# Schematic_Bottom_Rev2.net
KiCad netlist of a schematic drawn in Altium Designer
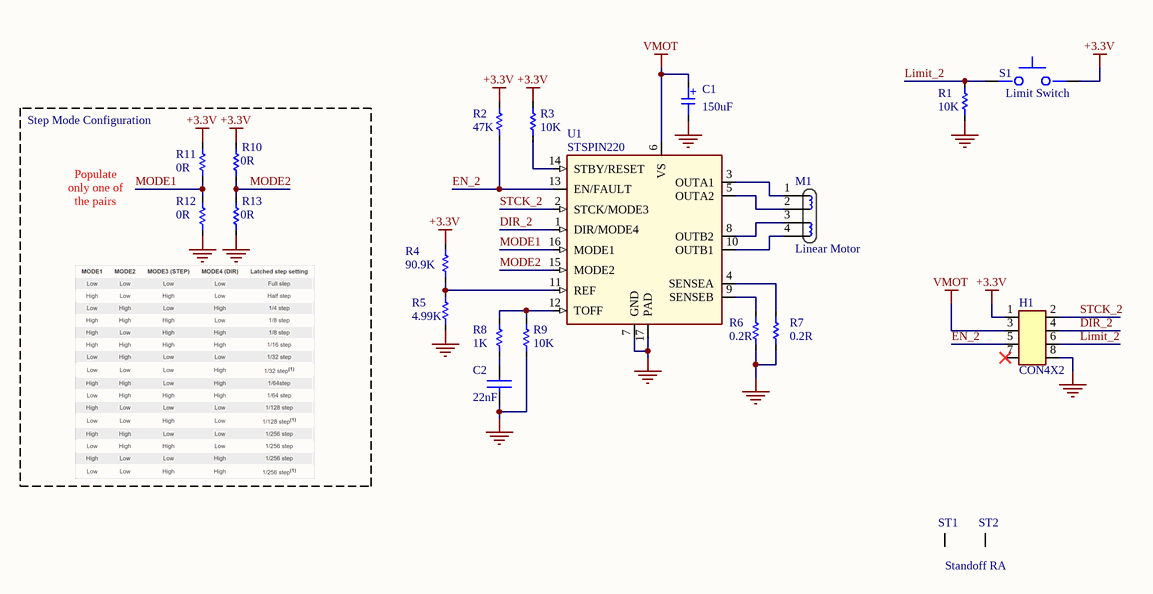
[diagram p0: Schematic_Bottom_Rev2.SchDoc]

(export (version "E")
  (design (tool "Eeschema 10.0.6"))
  (components
    (comp (ref "C1")
      (value "150uF")
      (footprint "CAP_SM_CAN_0.250_DIA")
      (description "CAP 150uF, 10V SMT")
      (fields (field (name "PART_NUMBER") "C242018") (field (name "MANUFACTURER") "Suncon"))
      (libsource (lib "MAR") (part "CAP_ELEC_SMT"))
    )
    (comp (ref "C2")
      (value "22nF")
      (footprint "CAPC1005X56N")
      (description "CAP 22nF 16V 0402")
      (fields (field (name "PART_NUMBER") "C318579") (field (name "MANUFACTURER") "Samsung"))
      (libsource (lib "MAR") (part "CAP_0402"))
    )
    (comp (ref "H1")
      (value "CON4X2")
      (footprint "RCPT2X4")
      (description "CONN REPT 4X2 POS .100\" RA")
      (fields (field (name "PART_NUMBER") "C92271") (field (name "MANUFACTURER") "CONNFLY"))
      (libsource (lib "MAR") (part "CON4X2_F"))
    )
    (comp (ref "M1")
      (value "Linear Motor")
      (footprint "Motor_Mini_Linear_1")
      (description "MTR,LINEAR,SMT")
      (fields (field (name "PART_NUMBER") "shorturl.at/cQ269"))
      (libsource (lib "MAR") (part "Motor_Mini_Linear"))
    )
    (comp (ref "R1")
      (value "10K")
      (footprint "RESC1005X40L")
      (description "RES 10K 0402")
      (fields (field (name "PART_NUMBER") "C25744") (field (name "MANUFACTURER") "Uniroyal"))
      (libsource (lib "MAR") (part "RES_0402"))
    )
    (comp (ref "R2")
      (value "47K")
      (footprint "RESC1005X40L")
      (description "RES 47K 0402")
      (fields (field (name "PART_NUMBER") "C25792") (field (name "MANUFACTURER") "Uniroyal"))
      (libsource (lib "MAR") (part "RES_0402"))
    )
    (comp (ref "R3")
      (value "10K")
      (footprint "RESC1005X40L")
      (description "RES 10K 0402")
      (fields (field (name "PART_NUMBER") "C25744") (field (name "MANUFACTURER") "Uniroyal"))
      (libsource (lib "MAR") (part "RES_0402"))
    )
    (comp (ref "R4")
      (value "90.9K")
      (footprint "RESC1005X40L")
      (description "RES 90.9K 0402")
      (fields (field (name "PART_NUMBER") "C26989") (field (name "MANUFACTURER") "Uniroyal"))
      (libsource (lib "MAR") (part "RES_0402"))
    )
    (comp (ref "R5")
      (value "4.99K")
      (footprint "RESC1005X40L")
      (description "RES 4.99K 0402")
      (fields (field (name "PART_NUMBER") "C25903") (field (name "MANUFACTURER") "Uniroyal"))
      (libsource (lib "MAR") (part "RES_0402"))
    )
    (comp (ref "R6")
      (value "0.2R")
      (footprint "RESC1005X40L")
      (description "RES 0.2R 0402")
      (fields (field (name "PART_NUMBER") "C270629") (field (name "MANUFACTURER") "Uniroyal"))
      (libsource (lib "MAR") (part "RES_0402"))
    )
    (comp (ref "R7")
      (value "0.2R")
      (footprint "RESC1005X40L")
      (description "RES 0.2R 0402")
      (fields (field (name "PART_NUMBER") "C270629") (field (name "MANUFACTURER") "Uniroyal"))
      (libsource (lib "MAR") (part "RES_0402"))
    )
    (comp (ref "R8")
      (value "1K")
      (footprint "RESC1005X40L")
      (description "RES 1K 0402")
      (fields (field (name "PART_NUMBER") "C11702") (field (name "MANUFACTURER") "Uniroyal"))
      (libsource (lib "MAR") (part "RES_0402"))
    )
    (comp (ref "R9")
      (value "10K")
      (footprint "RESC1005X40L")
      (description "RES 10K 0402")
      (fields (field (name "PART_NUMBER") "C25744") (field (name "MANUFACTURER") "Uniroyal"))
      (libsource (lib "MAR") (part "RES_0402"))
    )
    (comp (ref "R10")
      (value "0R")
      (footprint "RESC1005X40L")
      (description "RES 0R 0402")
      (fields (field (name "MANUFACTURER") "Uniroyal"))
      (libsource (lib "MAR") (part "RES_0402"))
    )
    (comp (ref "R11")
      (value "0R")
      (footprint "RESC1005X40L")
      (description "RES 0R 0402")
      (fields (field (name "MANUFACTURER") "Uniroyal"))
      (libsource (lib "MAR") (part "RES_0402"))
    )
    (comp (ref "R12")
      (value "0R")
      (footprint "RESC1005X40L")
      (description "RES 0R 0402")
      (fields (field (name "MANUFACTURER") "Uniroyal"))
      (libsource (lib "MAR") (part "RES_0402"))
    )
    (comp (ref "R13")
      (value "0R")
      (footprint "RESC1005X40L")
      (description "RES 0R 0402")
      (fields (field (name "MANUFACTURER") "Uniroyal"))
      (libsource (lib "MAR") (part "RES_0402"))
    )
    (comp (ref "S1")
      (value "Limit Switch")
      (footprint "SSCQ110100")
      (description "SWITCH DETECT, DUAL, SMD,R/A")
      (fields (field (name "PART_NUMBER") "C231760") (field (name "MANUFACTURER") "Alps"))
      (libsource (lib "MAR") (part "SSCQ110100"))
    )
    (comp (ref "ST1")
      (value "Standoff RA")
      (footprint "SMTRA440-9-6ET")
      (description "STANDOFF PCB RA 440 SMT")
      (fields (field (name "PART_NUMBER") "SMTRA440-9-6ET") (field (name "MANUFACTURER") "PENN"))
      (libsource (lib "MAR") (part "SMTRA440-9-6ET"))
    )
    (comp (ref "ST2")
      (value "Standoff RA")
      (footprint "SMTRA440-9-6ET")
      (description "STANDOFF PCB RA 440 SMT")
      (fields (field (name "PART_NUMBER") "SMTRA440-9-6ET") (field (name "MANUFACTURER") "PENN"))
      (libsource (lib "MAR") (part "SMTRA440-9-6ET"))
    )
    (comp (ref "U1")
      (value "STSPIN220")
      (footprint "16QFN")
      (description "IC STEPPER MOTOR DRIVER 16-VFQFPN(3x3)")
      (fields (field (name "MANUFACTURER") "ST Micro") (field (name "PART_NUMBER") "STSPIN220"))
      (libsource (lib "MAR") (part "STSPIN220"))
    )
  )
  (nets
    (net (code "1") (name "+3.3V") (class "Default")
      (node (ref "H1") (pin "1") (pintype "passive"))
      (node (ref "R10") (pin "1") (pintype "passive"))
      (node (ref "R11") (pin "2") (pintype "passive"))
      (node (ref "R2") (pin "2") (pintype "passive"))
      (node (ref "R3") (pin "2") (pintype "passive"))
      (node (ref "R4") (pin "2") (pintype "passive"))
      (node (ref "S1") (pin "2") (pinfunction "B_2") (pintype "passive"))
    )
    (net (code "2") (name "/DIR_2") (class "Default")
      (node (ref "H1") (pin "4") (pintype "passive"))
      (node (ref "U1") (pin "1") (pinfunction "DIR/MODE4_1") (pintype "input"))
    )
    (net (code "3") (name "/EN_2") (class "Default")
      (node (ref "H1") (pin "5") (pintype "passive"))
      (node (ref "R2") (pin "1") (pintype "passive"))
      (node (ref "U1") (pin "13") (pinfunction "EN/FAULT_13") (pintype "passive"))
    )
    (net (code "4") (name "/Limit_2") (class "Default")
      (node (ref "H1") (pin "6") (pintype "passive"))
      (node (ref "R1") (pin "1") (pintype "passive"))
      (node (ref "S1") (pin "1") (pinfunction "A_1") (pintype "passive"))
    )
    (net (code "5") (name "/MODE1") (class "Default")
      (node (ref "R11") (pin "1") (pintype "passive"))
      (node (ref "R12") (pin "1") (pintype "passive"))
      (node (ref "U1") (pin "16") (pinfunction "MODE1_16") (pintype "input"))
    )
    (net (code "6") (name "/MODE2") (class "Default")
      (node (ref "R10") (pin "2") (pintype "passive"))
      (node (ref "R13") (pin "1") (pintype "passive"))
      (node (ref "U1") (pin "15") (pinfunction "MODE2_15") (pintype "input"))
    )
    (net (code "7") (name "/STCK_2") (class "Default")
      (node (ref "H1") (pin "2") (pintype "passive"))
      (node (ref "U1") (pin "2") (pinfunction "STCK/MODE3_2") (pintype "input"))
    )
    (net (code "8") (name "GND") (class "Default")
      (node (ref "C1") (pin "2") (pintype "passive"))
      (node (ref "C2") (pin "2") (pinfunction "2_2") (pintype "passive"))
      (node (ref "H1") (pin "8") (pintype "passive"))
      (node (ref "R1") (pin "2") (pintype "passive"))
      (node (ref "R12") (pin "2") (pintype "passive"))
      (node (ref "R13") (pin "2") (pintype "passive"))
      (node (ref "R5") (pin "1") (pintype "passive"))
      (node (ref "R6") (pin "1") (pintype "passive"))
      (node (ref "R7") (pin "1") (pintype "passive"))
      (node (ref "R9") (pin "1") (pintype "passive"))
      (node (ref "U1") (pin "17") (pinfunction "PAD_17") (pintype "power_in"))
      (node (ref "U1") (pin "7") (pinfunction "GND_7") (pintype "power_in"))
    )
    (net (code "9") (name "Net-(C2-Pad1)") (class "Default")
      (node (ref "C2") (pin "1") (pinfunction "1_1") (pintype "passive"))
      (node (ref "R8") (pin "1") (pintype "passive"))
    )
    (net (code "10") (name "Net-(U1-OUTA1)") (class "Default")
      (node (ref "M1") (pin "1") (pintype "passive"))
      (node (ref "U1") (pin "3") (pinfunction "OUTA1_3") (pintype "passive"))
    )
    (net (code "11") (name "Net-(U1-OUTA2)") (class "Default")
      (node (ref "M1") (pin "2") (pintype "passive"))
      (node (ref "U1") (pin "5") (pinfunction "OUTA2_5") (pintype "passive"))
    )
    (net (code "12") (name "Net-(U1-OUTB1)") (class "Default")
      (node (ref "M1") (pin "4") (pintype "passive"))
      (node (ref "U1") (pin "10") (pinfunction "OUTB1_10") (pintype "passive"))
    )
    (net (code "13") (name "Net-(U1-OUTB2)") (class "Default")
      (node (ref "M1") (pin "3") (pintype "passive"))
      (node (ref "U1") (pin "8") (pinfunction "OUTB2_8") (pintype "passive"))
    )
    (net (code "14") (name "Net-(U1-REF)") (class "Default")
      (node (ref "R4") (pin "1") (pintype "passive"))
      (node (ref "R5") (pin "2") (pintype "passive"))
      (node (ref "U1") (pin "11") (pinfunction "REF_11") (pintype "input"))
    )
    (net (code "15") (name "Net-(U1-SENSEA)") (class "Default")
      (node (ref "R7") (pin "2") (pintype "passive"))
      (node (ref "U1") (pin "4") (pinfunction "SENSEA_4") (pintype "passive"))
    )
    (net (code "16") (name "Net-(U1-SENSEB)") (class "Default")
      (node (ref "R6") (pin "2") (pintype "passive"))
      (node (ref "U1") (pin "9") (pinfunction "SENSEB_9") (pintype "passive"))
    )
    (net (code "17") (name "Net-(U1-STBY{slash}RESET)") (class "Default")
      (node (ref "R3") (pin "1") (pintype "passive"))
      (node (ref "U1") (pin "14") (pinfunction "STBY/RESET_14") (pintype "input"))
    )
    (net (code "18") (name "Net-(U1-TOFF)") (class "Default")
      (node (ref "R8") (pin "2") (pintype "passive"))
      (node (ref "R9") (pin "2") (pintype "passive"))
      (node (ref "U1") (pin "12") (pinfunction "TOFF_12") (pintype "input"))
    )
    (net (code "19") (name "VMOT") (class "Default")
      (node (ref "C1") (pin "1") (pintype "passive"))
      (node (ref "H1") (pin "3") (pintype "passive"))
      (node (ref "U1") (pin "6") (pinfunction "VS_6") (pintype "power_in"))
    )
    (net (code "20") (name "unconnected-(H1-Pad7)") (class "Default")
      (node (ref "H1") (pin "7") (pintype "passive+no_connect"))
    )
    (net (code "21") (name "unconnected-(ST1-Pad1)") (class "Default")
      (node (ref "ST1") (pin "1") (pinfunction "1_1") (pintype "passive"))
    )
    (net (code "22") (name "unconnected-(ST2-Pad1)") (class "Default")
      (node (ref "ST2") (pin "1") (pinfunction "1_1") (pintype "passive"))
    )
  )
)
